# Sheet1.net
KiCad netlist of a schematic drawn in Altium Designer
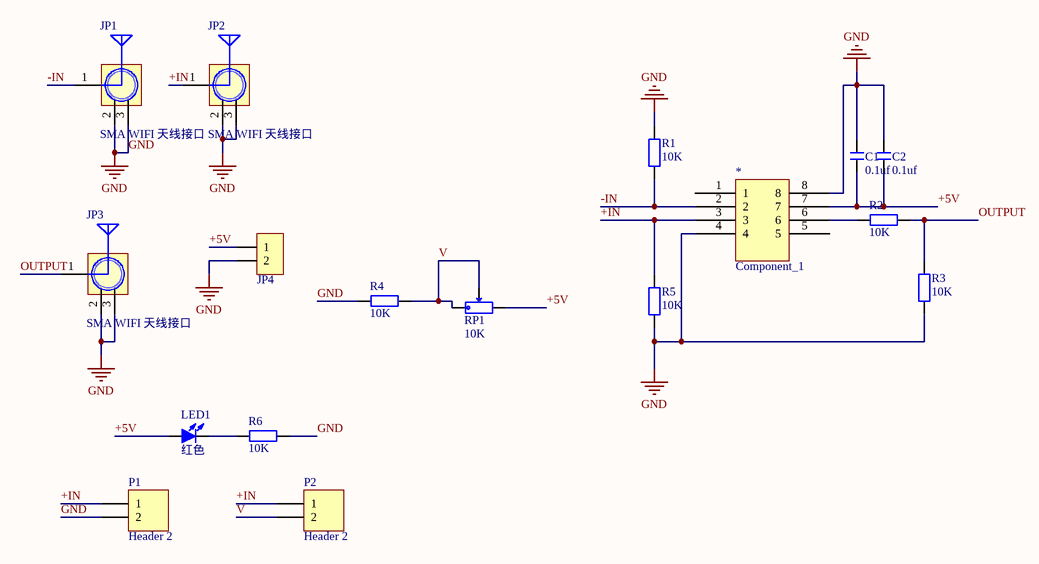
[diagram p0: Sheet1.SchDoc]

(export (version "E")
  (design (tool "Eeschema 10.0.6"))
  (components
    (comp (ref "*")
      (value "Component_1")
      (footprint "SOP8_N")
      (libsource (lib "Schlib1") (part "Component_1"))
    )
    (comp (ref "C1")
      (value "0.1uf")
      (footprint "C 0603_L")
      (description "贴片电容")
      (libsource (lib "实验室") (part "C"))
    )
    (comp (ref "C2")
      (value "0.1uf")
      (footprint "C 0603_L")
      (description "贴片电容")
      (libsource (lib "实验室") (part "C"))
    )
    (comp (ref "JP1")
      (value "SMA WIFI 天线接口")
      (footprint "SMA-KE")
      (description "SMA-2.4G射频天线接口")
      (fields (field (name "版权归属") "封装库来自淘宝 ID：黄晶宝石"))
      (libsource (lib "1.8 - WiFi天线-SMA射频座") (part "SMA"))
    )
    (comp (ref "JP2")
      (value "SMA WIFI 天线接口")
      (footprint "SMA-KE")
      (description "SMA-2.4G射频天线接口")
      (fields (field (name "版权归属") "封装库来自淘宝 ID：黄晶宝石"))
      (libsource (lib "1.8 - WiFi天线-SMA射频座") (part "SMA"))
    )
    (comp (ref "JP3")
      (value "SMA WIFI 天线接口")
      (footprint "SMA-KE")
      (description "SMA-2.4G射频天线接口")
      (fields (field (name "版权归属") "封装库来自淘宝 ID：黄晶宝石"))
      (libsource (lib "1.8 - WiFi天线-SMA射频座") (part "SMA"))
    )
    (comp (ref "JP4")
      (value "HDR-1X2")
      (footprint "XH2.54-LI-2P")
      (description "2P接插件")
      (libsource (lib "XH2.54") (part "Header 2"))
    )
    (comp (ref "LED1")
      (value "红色")
      (footprint "LED 0805R")
      (description "贴片LED")
      (fields (field (name "版权归属") "源创客"))
      (libsource (lib "实验室") (part "LED-SMD"))
    )
    (comp (ref "P1")
      (value "Header 2")
      (footprint "HDR1X2")
      (description "Header, 2-Pin")
      (fields (field (name "PUBLISHER") "Altium Limited"))
      (libsource (lib "Miscellaneous Connectors") (part "Header 2"))
    )
    (comp (ref "P2")
      (value "Header 2")
      (footprint "HDR1X2")
      (description "Header, 2-Pin")
      (fields (field (name "PUBLISHER") "Altium Limited"))
      (libsource (lib "Miscellaneous Connectors") (part "Header 2"))
    )
    (comp (ref "R1")
      (value "10K")
      (footprint "R 0805_L")
      (description "贴片电阻")
      (fields (field (name "版权归属") "来自淘宝 ID：黄晶宝石"))
      (libsource (lib "实验室") (part "R"))
    )
    (comp (ref "R2")
      (value "10K")
      (footprint "R 0805_L")
      (description "贴片电阻")
      (fields (field (name "版权归属") "来自淘宝 ID：黄晶宝石"))
      (libsource (lib "实验室") (part "R"))
    )
    (comp (ref "R3")
      (value "10K")
      (footprint "R 0805_L")
      (description "贴片电阻")
      (fields (field (name "版权归属") "来自淘宝 ID：黄晶宝石"))
      (libsource (lib "实验室") (part "R"))
    )
    (comp (ref "R4")
      (value "10K")
      (footprint "R 0805_L")
      (description "贴片电阻")
      (fields (field (name "版权归属") "来自淘宝 ID：黄晶宝石"))
      (libsource (lib "实验室") (part "R"))
    )
    (comp (ref "R5")
      (value "10K")
      (footprint "R 0805_L")
      (description "贴片电阻")
      (fields (field (name "版权归属") "来自淘宝 ID：黄晶宝石"))
      (libsource (lib "实验室") (part "R"))
    )
    (comp (ref "R6")
      (value "10K")
      (footprint "R 0805_L")
      (description "贴片电阻")
      (fields (field (name "版权归属") "来自淘宝 ID：黄晶宝石"))
      (libsource (lib "实验室") (part "R"))
    )
    (comp (ref "RP1")
      (value "10K")
      (footprint "3303W")
      (description "插件单联电位器")
      (libsource (lib "电容-电阻-电感-电位器") (part "RP-ID"))
    )
  )
  (nets
    (net (code "1") (name "/+5V") (class "Default")
      (node (ref "*") (pin "7") (pinfunction "7_7") (pintype "passive"))
      (node (ref "C1") (pin "1") (pinfunction "1_1") (pintype "passive"))
      (node (ref "C2") (pin "1") (pinfunction "1_1") (pintype "passive"))
      (node (ref "JP4") (pin "1") (pinfunction "1_1") (pintype "passive"))
      (node (ref "LED1") (pin "1") (pinfunction "A_1") (pintype "passive"))
      (node (ref "RP1") (pin "3") (pinfunction "3_3") (pintype "passive"))
    )
    (net (code "2") (name "/+IN") (class "Default")
      (node (ref "*") (pin "3") (pinfunction "3_3") (pintype "passive"))
      (node (ref "JP2") (pin "1") (pinfunction "ANT_1") (pintype "passive"))
      (node (ref "P1") (pin "1") (pinfunction "1_1") (pintype "passive"))
      (node (ref "P2") (pin "1") (pinfunction "1_1") (pintype "passive"))
      (node (ref "R5") (pin "1") (pinfunction "1_1") (pintype "passive"))
    )
    (net (code "3") (name "/-IN") (class "Default")
      (node (ref "*") (pin "2") (pinfunction "2_2") (pintype "passive"))
      (node (ref "JP1") (pin "1") (pinfunction "ANT_1") (pintype "passive"))
      (node (ref "R1") (pin "1") (pinfunction "1_1") (pintype "passive"))
    )
    (net (code "4") (name "/OUTPUT") (class "Default")
      (node (ref "JP3") (pin "1") (pinfunction "ANT_1") (pintype "passive"))
      (node (ref "R2") (pin "2") (pinfunction "2_2") (pintype "passive"))
      (node (ref "R3") (pin "2") (pinfunction "2_2") (pintype "passive"))
    )
    (net (code "5") (name "/V") (class "Default")
      (node (ref "P2") (pin "2") (pinfunction "2_2") (pintype "passive"))
      (node (ref "R4") (pin "1") (pinfunction "1_1") (pintype "passive"))
      (node (ref "RP1") (pin "1") (pinfunction "1_1") (pintype "passive"))
      (node (ref "RP1") (pin "2") (pinfunction "2_2") (pintype "passive"))
    )
    (net (code "6") (name "GND") (class "Default")
      (node (ref "*") (pin "4") (pinfunction "4_4") (pintype "passive"))
      (node (ref "*") (pin "8") (pinfunction "8_8") (pintype "passive"))
      (node (ref "C1") (pin "2") (pinfunction "2_2") (pintype "passive"))
      (node (ref "C2") (pin "2") (pinfunction "2_2") (pintype "passive"))
      (node (ref "JP1") (pin "2") (pinfunction "GND_2") (pintype "passive"))
      (node (ref "JP1") (pin "3") (pinfunction "GND_3") (pintype "passive"))
      (node (ref "JP2") (pin "2") (pinfunction "GND_2") (pintype "passive"))
      (node (ref "JP2") (pin "3") (pinfunction "GND_3") (pintype "passive"))
      (node (ref "JP3") (pin "2") (pinfunction "GND_2") (pintype "passive"))
      (node (ref "JP3") (pin "3") (pinfunction "GND_3") (pintype "passive"))
      (node (ref "JP4") (pin "2") (pinfunction "2_2") (pintype "passive"))
      (node (ref "P1") (pin "2") (pinfunction "2_2") (pintype "passive"))
      (node (ref "R1") (pin "2") (pinfunction "2_2") (pintype "passive"))
      (node (ref "R3") (pin "1") (pinfunction "1_1") (pintype "passive"))
      (node (ref "R4") (pin "2") (pinfunction "2_2") (pintype "passive"))
      (node (ref "R5") (pin "2") (pinfunction "2_2") (pintype "passive"))
      (node (ref "R6") (pin "2") (pinfunction "2_2") (pintype "passive"))
    )
    (net (code "7") (name "Net-(*-Pad6)") (class "Default")
      (node (ref "*") (pin "6") (pinfunction "6_6") (pintype "passive"))
      (node (ref "R2") (pin "1") (pinfunction "1_1") (pintype "passive"))
    )
    (net (code "8") (name "Net-(LED1-K)") (class "Default")
      (node (ref "LED1") (pin "2") (pinfunction "K_2") (pintype "passive"))
      (node (ref "R6") (pin "1") (pinfunction "1_1") (pintype "passive"))
    )
    (net (code "9") (name "unconnected-(*-Pad1)") (class "Default")
      (node (ref "*") (pin "1") (pinfunction "1_1") (pintype "passive"))
    )
    (net (code "10") (name "unconnected-(*-Pad5)") (class "Default")
      (node (ref "*") (pin "5") (pinfunction "5_5") (pintype "passive"))
    )
  )
)
